# MainBoard_Motor2.net
KiCad netlist of a schematic drawn in Altium Designer
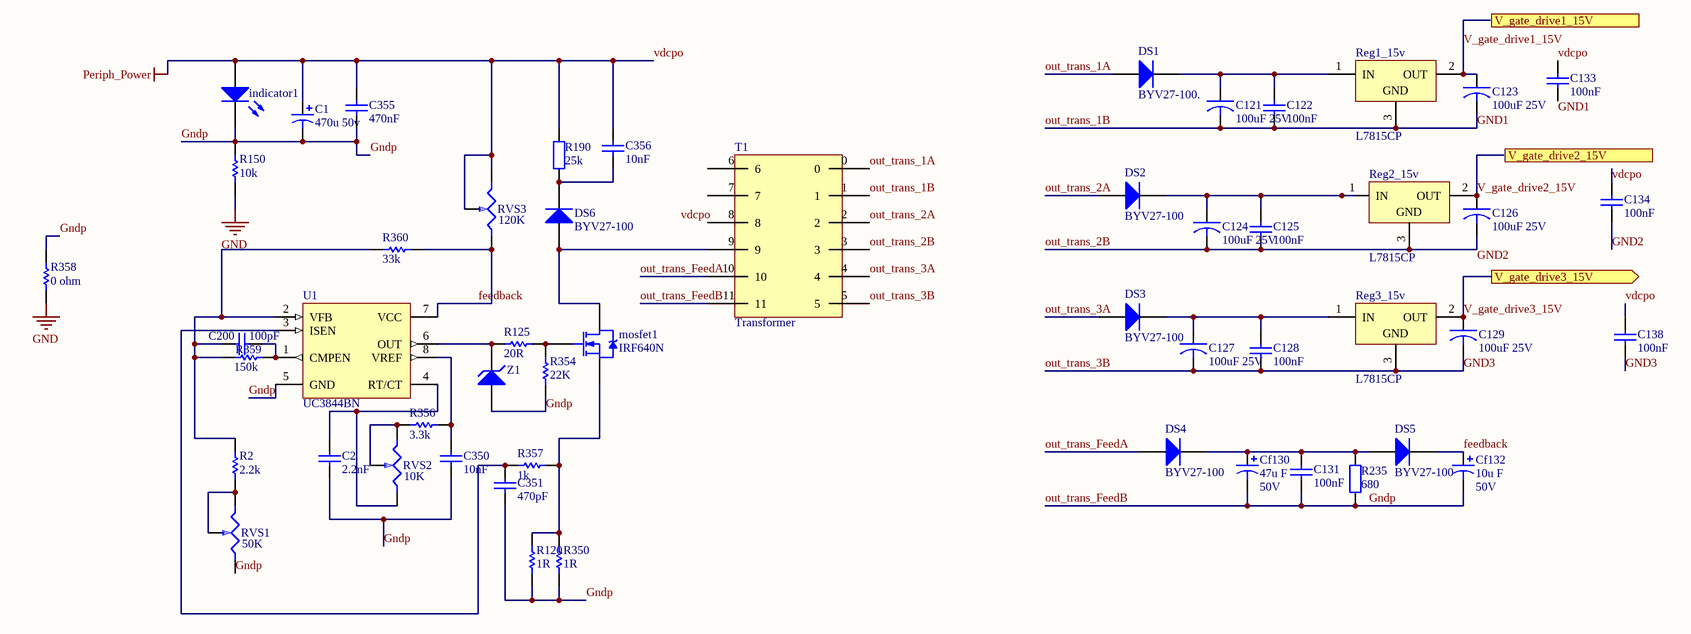
[diagram p0: MainBoard_Motor2.SchDoc]

(export (version "E")
  (design (tool "Eeschema 10.0.6"))
  (components
    (comp (ref "C1")
      (value "470u 50v")
      (footprint "CAPPR5-5x5")
      (description "Polarized Capacitor (Radial)")
      (fields (field (name "PUBLISHER") "Altium Limited"))
      (libsource (lib "Miscellaneous Devices") (part "Cap Pol1"))
    )
    (comp (ref "C2")
      (value "2.2nF")
      (footprint "C0805")
      (description "Cap_2.2nF_10%_X7R_50V_0805")
      (fields (field (name "MANUFACTURER") "Yageo") (field (name "MFR PART NO") "CC0805KRX7R9BB103"))
      (libsource (lib "EVIDC") (part "Cap_10nF_50V_0805"))
    )
    (comp (ref "C121")
      (value "100uF 25V")
      (footprint "EVIDC:CAP_E_6.3x9_2.5")
      (description "Cap_100uF 25V_Pitch2.5mm")
      (fields (field (name "MFR PART NO") "ERS1EM101E11OT") (field (name "MANUFACTURER") "AIHUA"))
      (libsource (lib "EVIDC") (part "Cap_100uF 25V_EL_6.3MM"))
    )
    (comp (ref "C122")
      (value "100nF")
      (footprint "C0805")
      (description "Cap_10nF_10%_X7R_50V_0805")
      (fields (field (name "MANUFACTURER") "Yageo") (field (name "MFR PART NO") "CC0805KRX7R9BB103"))
      (libsource (lib "EVIDC") (part "Cap_10nF_50V_0805"))
    )
    (comp (ref "C123")
      (value "100uF 25V")
      (footprint "EVIDC:CAP_E_6.3x9_2.5")
      (description "Cap_100uF 25V_Pitch2.5mm")
      (fields (field (name "MFR PART NO") "ERS1EM101E11OT") (field (name "MANUFACTURER") "AIHUA"))
      (libsource (lib "EVIDC") (part "Cap_100uF 25V_EL_6.3MM"))
    )
    (comp (ref "C124")
      (value "100uF 25V")
      (footprint "EVIDC:CAP_E_6.3x9_2.5")
      (description "Cap_100uF 25V_Pitch2.5mm")
      (fields (field (name "MFR PART NO") "ERS1EM101E11OT") (field (name "MANUFACTURER") "AIHUA"))
      (libsource (lib "EVIDC") (part "Cap_100uF 25V_EL_6.3MM"))
    )
    (comp (ref "C125")
      (value "100nF")
      (footprint "C0805")
      (description "Cap_10nF_10%_X7R_50V_0805")
      (fields (field (name "MANUFACTURER") "Yageo") (field (name "MFR PART NO") "CC0805KRX7R9BB103"))
      (libsource (lib "EVIDC") (part "Cap_10nF_50V_0805"))
    )
    (comp (ref "C126")
      (value "100uF 25V")
      (footprint "EVIDC:CAP_E_6.3x9_2.5")
      (description "Cap_100uF 25V_Pitch2.5mm")
      (fields (field (name "MFR PART NO") "ERS1EM101E11OT") (field (name "MANUFACTURER") "AIHUA"))
      (libsource (lib "EVIDC") (part "Cap_100uF 25V_EL_6.3MM"))
    )
    (comp (ref "C127")
      (value "100uF 25V")
      (footprint "EVIDC:CAP_E_6.3x9_2.5")
      (description "Cap_100uF 25V_Pitch2.5mm")
      (fields (field (name "MFR PART NO") "ERS1EM101E11OT") (field (name "MANUFACTURER") "AIHUA"))
      (libsource (lib "EVIDC") (part "Cap_100uF 25V_EL_6.3MM"))
    )
    (comp (ref "C128")
      (value "100nF")
      (footprint "C0805")
      (description "Cap_10nF_10%_X7R_50V_0805")
      (fields (field (name "MANUFACTURER") "Yageo") (field (name "MFR PART NO") "CC0805KRX7R9BB103"))
      (libsource (lib "EVIDC") (part "Cap_10nF_50V_0805"))
    )
    (comp (ref "C129")
      (value "100uF 25V")
      (footprint "EVIDC:CAP_E_6.3x9_2.5")
      (description "Cap_100uF 25V_Pitch2.5mm")
      (fields (field (name "MFR PART NO") "ERS1EM101E11OT") (field (name "MANUFACTURER") "AIHUA"))
      (libsource (lib "EVIDC") (part "Cap_100uF 25V_EL_6.3MM"))
    )
    (comp (ref "C131")
      (value "100nF")
      (footprint "C0805")
      (description "Cap_10nF_10%_X7R_50V_0805")
      (fields (field (name "MANUFACTURER") "Yageo") (field (name "MFR PART NO") "CC0805KRX7R9BB103"))
      (libsource (lib "EVIDC") (part "Cap_10nF_50V_0805"))
    )
    (comp (ref "C133")
      (value "100nF")
      (footprint "C0805")
      (description "Cap_10nF_10%_X7R_50V_0805")
      (fields (field (name "MANUFACTURER") "Yageo") (field (name "MFR PART NO") "CC0805KRX7R9BB103"))
      (libsource (lib "EVIDC") (part "Cap_10nF_50V_0805"))
    )
    (comp (ref "C134")
      (value "100nF")
      (footprint "C0805")
      (description "Cap_10nF_10%_X7R_50V_0805")
      (fields (field (name "MANUFACTURER") "Yageo") (field (name "MFR PART NO") "CC0805KRX7R9BB103"))
      (libsource (lib "EVIDC") (part "Cap_10nF_50V_0805"))
    )
    (comp (ref "C138")
      (value "100nF")
      (footprint "C0805")
      (description "Cap_10nF_10%_X7R_50V_0805")
      (fields (field (name "MANUFACTURER") "Yageo") (field (name "MFR PART NO") "CC0805KRX7R9BB103"))
      (libsource (lib "EVIDC") (part "Cap_10nF_50V_0805"))
    )
    (comp (ref "C200")
      (value "100pF")
      (footprint "EVIDC:C0805")
      (description "Cap_100pF_10%_X7R_50V_0805")
      (fields (field (name "MANUFACTURER") "Yageo") (field (name "MFR PART NO") "CC0805KRX7R9BB101"))
      (libsource (lib "EVIDC") (part "Cap_100pF_50V_0805"))
    )
    (comp (ref "C350")
      (value "10nF")
      (footprint "C0805")
      (description "Cap_10nF_10%_X7R_50V_0805")
      (fields (field (name "MANUFACTURER") "Yageo") (field (name "MFR PART NO") "CC0805KRX7R9BB103"))
      (libsource (lib "EVIDC") (part "Cap_10nF_50V_0805"))
    )
    (comp (ref "C351")
      (value "470pF")
      (footprint "C0805")
      (description "Cap_10nF_10%_X7R_50V_0805")
      (fields (field (name "MANUFACTURER") "Yageo") (field (name "MFR PART NO") "CC0805KRX7R9BB103"))
      (libsource (lib "EVIDC") (part "Cap_10nF_50V_0805"))
    )
    (comp (ref "C355")
      (value "470nF")
      (footprint "C0805")
      (description "Cap_10nF_10%_X7R_50V_0805")
      (fields (field (name "MANUFACTURER") "Yageo") (field (name "MFR PART NO") "CC0805KRX7R9BB103"))
      (libsource (lib "EVIDC") (part "Cap_10nF_50V_0805"))
    )
    (comp (ref "C356")
      (value "10nF")
      (footprint "C0805")
      (description "Cap_10nF_10%_X7R_50V_0805")
      (fields (field (name "MANUFACTURER") "Yageo") (field (name "MFR PART NO") "CC0805KRX7R9BB103"))
      (libsource (lib "EVIDC") (part "Cap_10nF_50V_0805"))
    )
    (comp (ref "Cf130")
      (value "47u F")
      (footprint "B")
      (description "Polarized Capacitor (Radial)")
      (fields (field (name "ALTIUM_VALUE") "50V") (field (name "PUBLISHER") "Altium Limited"))
      (libsource (lib "Miscellaneous Devices") (part "Cap Pol1"))
    )
    (comp (ref "Cf132")
      (value "10u F")
      (footprint "B")
      (description "Polarized Capacitor (Radial)")
      (fields (field (name "ALTIUM_VALUE") "50V") (field (name "PUBLISHER") "Altium Limited"))
      (libsource (lib "Miscellaneous Devices") (part "Cap Pol1"))
    )
    (comp (ref "DS1")
      (value "BYV27-100.")
      (footprint "DO-41")
      (description "1 Amp General Purpose Rectifier SMD")
      (fields (field (name "PUBLISHER") "Altium Limited"))
      (libsource (lib "Miscellaneous Devices") (part "Diode 1N4007"))
    )
    (comp (ref "DS2")
      (value "BYV27-100")
      (footprint "DO-41")
      (description "1 Amp General Purpose Rectifier SMD")
      (fields (field (name "PUBLISHER") "Altium Limited"))
      (libsource (lib "Miscellaneous Devices") (part "Diode 1N4007"))
    )
    (comp (ref "DS3")
      (value "BYV27-100")
      (footprint "DO-41")
      (description "1 Amp General Purpose Rectifier SMD")
      (fields (field (name "PUBLISHER") "Altium Limited"))
      (libsource (lib "Miscellaneous Devices") (part "Diode 1N4007"))
    )
    (comp (ref "DS4")
      (value "BYV27-100")
      (footprint "DO-41")
      (description "1 Amp General Purpose Rectifier SMD")
      (fields (field (name "PUBLISHER") "Altium Limited"))
      (libsource (lib "Miscellaneous Devices") (part "Diode 1N4007"))
    )
    (comp (ref "DS5")
      (value "BYV27-100")
      (footprint "DO-41")
      (description "1 Amp General Purpose Rectifier SMD")
      (fields (field (name "PUBLISHER") "Altium Limited"))
      (libsource (lib "Miscellaneous Devices") (part "Diode 1N4007"))
    )
    (comp (ref "DS6")
      (value "BYV27-100")
      (footprint "DO-41")
      (description "1 Amp General Purpose Rectifier")
      (fields (field (name "PUBLISHER") "Altium Limited"))
      (libsource (lib "Miscellaneous Devices") (part "Diode 1N4007"))
    )
    (comp (ref "indicator1")
      (value "GREEN")
      (footprint "EVIDC:LED_0805_GREEN")
      (description "Typical BLUE SiC LED")
      (fields
        (field (name "MANUFACTURER") "Kingbright")
        (field (name "MFR PART NO") "APT2012SGC")
        (field (name "PUBLISHER") "Altium Limited")
      )
      (libsource (lib "Miscellaneous Devices") (part "LED3"))
    )
    (comp (ref "mosfet1")
      (value "IRF640N")
      (footprint "TO-220AB")
      (description "HEXFET Power MOSFET")
      (fields (field (name "PUBLISHER") "Altium Limited"))
      (libsource (lib "IR Discrete MOSFET - Power") (part "IRF640N"))
    )
    (comp (ref "R2")
      (value "2.2k")
      (footprint "EVIDC:R0805")
      (description "Res_2.2K_1%_0805")
      (fields (field (name "MANUFACTURER") "Yageo") (field (name "MFR PART NO") "RC0805FR-074K7L"))
      (libsource (lib "EVIDC") (part "Res_4.7K_0805"))
    )
    (comp (ref "R120")
      (value "1R")
      (footprint "EVIDC:R1206")
      (description "Res_2.2R_1%_1206")
      (fields (field (name "MANUFACTURER") "Yageo") (field (name "MFR PART NO") "RC1206FR-072R2L"))
      (libsource (lib "EVIDC") (part "Res_2.2R_1206"))
    )
    (comp (ref "R125")
      (value "20R")
      (footprint "EVIDC:R1206")
      (description "Res_20R_1%_0.25W_1206")
      (fields (field (name "MANUFACTURER") "Yageo") (field (name "MFR PART NO") "RC1206FR-0720RL"))
      (libsource (lib "EVIDC") (part "Res_20R_1206"))
    )
    (comp (ref "R150")
      (value "10k")
      (footprint "EVIDC:R1206")
      (description "Res_20R_1%_0.25W_1206")
      (fields (field (name "MANUFACTURER") "Yageo") (field (name "MFR PART NO") "RC1206FR-0720RL"))
      (libsource (lib "EVIDC") (part "Res_20R_1206"))
    )
    (comp (ref "R190")
      (value "25k")
      (footprint "AXIAL-0.6")
      (description "Resistor")
      (fields (field (name "PUBLISHER") "Altium Limited"))
      (libsource (lib "Miscellaneous Devices") (part "Res2"))
    )
    (comp (ref "R235")
      (value "680")
      (footprint "AXIAL-0.5")
      (description "Resistor")
      (fields (field (name "PUBLISHER") "Altium Limited"))
      (libsource (lib "Miscellaneous Devices") (part "Res2"))
    )
    (comp (ref "R350")
      (value "1R")
      (footprint "EVIDC:R1206")
      (description "Res_2.2R_1%_1206")
      (fields (field (name "MANUFACTURER") "Yageo") (field (name "MFR PART NO") "RC1206FR-072R2L"))
      (libsource (lib "EVIDC") (part "Res_2.2R_1206"))
    )
    (comp (ref "R354")
      (value "22K")
      (footprint "EVIDC:R0805")
      (description "Res_4.7K_1%_0805")
      (fields (field (name "MANUFACTURER") "Yageo") (field (name "MFR PART NO") "RC0805FR-074K7L"))
      (libsource (lib "EVIDC") (part "Res_4.7K_0805"))
    )
    (comp (ref "R356")
      (value "3.3k")
      (footprint "EVIDC:R0805")
      (description "Res_2.2K_1%_0805")
      (fields (field (name "MANUFACTURER") "Yageo") (field (name "MFR PART NO") "RC0805FR-074K7L"))
      (libsource (lib "EVIDC") (part "Res_4.7K_0805"))
    )
    (comp (ref "R357")
      (value "1k")
      (footprint "EVIDC:R0805")
      (description "Res_2.2K_1%_0805")
      (fields (field (name "MANUFACTURER") "Yageo") (field (name "MFR PART NO") "RC0805FR-074K7L"))
      (libsource (lib "EVIDC") (part "Res_4.7K_0805"))
    )
    (comp (ref "R358")
      (value "0 ohm")
      (footprint "EVIDC:R0805")
      (description "Res_2.2K_1%_0805")
      (fields (field (name "MANUFACTURER") "Yageo") (field (name "MFR PART NO") "RC0805FR-074K7L"))
      (libsource (lib "EVIDC") (part "Res_4.7K_0805"))
    )
    (comp (ref "R359")
      (value "150k")
      (footprint "EVIDC:R1206")
      (description "Res_20R_1%_0.25W_1206")
      (fields (field (name "MANUFACTURER") "Yageo") (field (name "MFR PART NO") "RC1206FR-0720RL"))
      (libsource (lib "EVIDC") (part "Res_20R_1206"))
    )
    (comp (ref "R360")
      (value "33k")
      (footprint "EVIDC:R1206")
      (description "Res_20R_1%_0.25W_1206")
      (fields (field (name "MANUFACTURER") "Yageo") (field (name "MFR PART NO") "RC1206FR-0720RL"))
      (libsource (lib "EVIDC") (part "Res_20R_1206"))
    )
    (comp (ref "Reg1_15v")
      (value "L7815CP")
      (footprint "TO220VW")
      (description "2A Positive Voltage Regulator")
      (fields (field (name "PUBLISHER") "Altium Limited"))
      (libsource (lib "ST Power Mgt Voltage Regulator") (part "L78S05CV"))
    )
    (comp (ref "Reg2_15v")
      (value "L7815CP")
      (footprint "TO220VW")
      (description "2A Positive Voltage Regulator")
      (fields (field (name "PUBLISHER") "Altium Limited"))
      (libsource (lib "ST Power Mgt Voltage Regulator") (part "L78S05CV"))
    )
    (comp (ref "Reg3_15v")
      (value "L7815CP")
      (footprint "TO220VW")
      (description "2A Positive Voltage Regulator")
      (fields (field (name "PUBLISHER") "Altium Limited"))
      (libsource (lib "ST Power Mgt Voltage Regulator") (part "L78S05CV"))
    )
    (comp (ref "RVS1") (value "50K") (footprint "VR5") (libsource (lib "*") (part "RESISTOR VAR")))
    (comp (ref "RVS2") (value "10K") (footprint "VR5") (libsource (lib "*") (part "RESISTOR VAR")))
    (comp (ref "RVS3") (value "120K") (footprint "VR5") (libsource (lib "*") (part "RESISTOR VAR")))
    (comp (ref "T1") (value "Transformer") (libsource (lib "Integrated_Library2") (part "Component_1")))
    (comp (ref "U1")
      (value "UC3844BN")
      (footprint "626-05")
      (description "High Performance Current Mode Controller")
      (fields (field (name "PUBLISHER") "Altium Limited"))
      (libsource (lib "ON Semi Power Mgt DC-DC Converter") (part "UC3844BN"))
    )
    (comp (ref "Z1")
      (value "D Zener")
      (footprint "DO-35")
      (description "Half Watt Zener")
      (fields (field (name "PUBLISHER") "Altium Limited"))
      (libsource (lib "FSC Discrete Diode") (part "1N751A"))
    )
  )
  (nets
    (net (code "1") (name "/GND1") (class "Default")
      (node (ref "C121") (pin "2") (pinfunction "2_2") (pintype "passive"))
      (node (ref "C122") (pin "1") (pinfunction "1_1") (pintype "passive"))
      (node (ref "C123") (pin "2") (pinfunction "2_2") (pintype "passive"))
      (node (ref "Reg1_15v") (pin "3") (pinfunction "GND_3") (pintype "power_in"))
      (node (ref "T1") (pin "1") (pinfunction "1_1") (pintype "passive"))
    )
    (net (code "2") (name "/GND2") (class "Default")
      (node (ref "C134") (pin "1") (pinfunction "1_1") (pintype "passive"))
    )
    (net (code "3") (name "/GND3") (class "Default")
      (node (ref "C127") (pin "2") (pinfunction "2_2") (pintype "passive"))
      (node (ref "C128") (pin "1") (pinfunction "1_1") (pintype "passive"))
      (node (ref "C129") (pin "2") (pinfunction "2_2") (pintype "passive"))
      (node (ref "C138") (pin "1") (pinfunction "1_1") (pintype "passive"))
      (node (ref "Reg3_15v") (pin "3") (pinfunction "GND_3") (pintype "power_in"))
      (node (ref "T1") (pin "5") (pinfunction "5_5") (pintype "passive"))
    )
    (net (code "4") (name "/Gndp") (class "Default")
      (node (ref "C1") (pin "2") (pinfunction "2_2") (pintype "passive"))
      (node (ref "C131") (pin "1") (pinfunction "1_1") (pintype "passive"))
      (node (ref "C2") (pin "1") (pinfunction "1_1") (pintype "passive"))
      (node (ref "C350") (pin "1") (pinfunction "1_1") (pintype "passive"))
      (node (ref "C351") (pin "1") (pinfunction "1_1") (pintype "passive"))
      (node (ref "C355") (pin "1") (pinfunction "1_1") (pintype "passive"))
      (node (ref "Cf130") (pin "2") (pinfunction "2_2") (pintype "passive"))
      (node (ref "Cf132") (pin "2") (pinfunction "2_2") (pintype "passive"))
      (node (ref "R120") (pin "2") (pinfunction "2_2") (pintype "passive"))
      (node (ref "R150") (pin "2") (pinfunction "2_2") (pintype "passive"))
      (node (ref "R235") (pin "1") (pinfunction "1_1") (pintype "passive"))
      (node (ref "R350") (pin "2") (pinfunction "2_2") (pintype "passive"))
      (node (ref "R354") (pin "1") (pinfunction "1_1") (pintype "passive"))
      (node (ref "R358") (pin "2") (pinfunction "2_2") (pintype "passive"))
      (node (ref "RVS1") (pin "3") (pinfunction "B_3") (pintype "passive"))
      (node (ref "T1") (pin "11") (pinfunction "11_11") (pintype "passive"))
      (node (ref "U1") (pin "5") (pinfunction "GND_5") (pintype "power_in"))
      (node (ref "Z1") (pin "1") (pinfunction "A_1") (pintype "passive"))
      (node (ref "indicator1") (pin "2") (pinfunction "K_2") (pintype "passive"))
    )
    (net (code "5") (name "/V_gate_drive1_15V") (class "Default")
      (node (ref "C123") (pin "1") (pinfunction "1_1") (pintype "passive"))
      (node (ref "Reg1_15v") (pin "2") (pinfunction "OUT_2") (pintype "power_in"))
    )
    (net (code "6") (name "/V_gate_drive2_15V") (class "Default")
      (node (ref "C126") (pin "1") (pinfunction "1_1") (pintype "passive"))
      (node (ref "Reg2_15v") (pin "2") (pinfunction "OUT_2") (pintype "power_in"))
    )
    (net (code "7") (name "/V_gate_drive3_15V") (class "Default")
      (node (ref "C129") (pin "1") (pinfunction "1_1") (pintype "passive"))
      (node (ref "Reg3_15v") (pin "2") (pinfunction "OUT_2") (pintype "power_in"))
    )
    (net (code "8") (name "/feedback") (class "Default")
      (node (ref "Cf132") (pin "1") (pinfunction "1_1") (pintype "passive"))
      (node (ref "DS5") (pin "2") (pinfunction "K_2") (pintype "passive"))
      (node (ref "R360") (pin "2") (pinfunction "2_2") (pintype "passive"))
      (node (ref "RVS3") (pin "3") (pinfunction "B_3") (pintype "passive"))
      (node (ref "U1") (pin "7") (pinfunction "VCC_7") (pintype "power_in"))
    )
    (net (code "9") (name "/out_trans_1A") (class "Default")
      (node (ref "DS1") (pin "1") (pinfunction "A_1") (pintype "passive"))
      (node (ref "T1") (pin "0") (pinfunction "0_0") (pintype "passive"))
    )
    (net (code "10") (name "/out_trans_2A") (class "Default")
      (node (ref "DS2") (pin "1") (pinfunction "A_1") (pintype "passive"))
      (node (ref "T1") (pin "2") (pinfunction "2_2") (pintype "passive"))
    )
    (net (code "11") (name "/out_trans_2B") (class "Default")
      (node (ref "C124") (pin "2") (pinfunction "2_2") (pintype "passive"))
      (node (ref "C125") (pin "1") (pinfunction "1_1") (pintype "passive"))
      (node (ref "C126") (pin "2") (pinfunction "2_2") (pintype "passive"))
      (node (ref "Reg2_15v") (pin "3") (pinfunction "GND_3") (pintype "power_in"))
      (node (ref "T1") (pin "3") (pinfunction "3_3") (pintype "passive"))
    )
    (net (code "12") (name "/out_trans_3A") (class "Default")
      (node (ref "DS3") (pin "1") (pinfunction "A_1") (pintype "passive"))
      (node (ref "T1") (pin "4") (pinfunction "4_4") (pintype "passive"))
    )
    (net (code "13") (name "/out_trans_FeedA") (class "Default")
      (node (ref "DS4") (pin "1") (pinfunction "A_1") (pintype "passive"))
      (node (ref "T1") (pin "10") (pinfunction "10_10") (pintype "passive"))
    )
    (net (code "14") (name "GND") (class "Default")
      (node (ref "R150") (pin "1") (pinfunction "1_1") (pintype "passive"))
      (node (ref "R358") (pin "1") (pinfunction "1_1") (pintype "passive"))
    )
    (net (code "15") (name "Net-(DS1-K)") (class "Default")
      (node (ref "C121") (pin "1") (pinfunction "1_1") (pintype "passive"))
      (node (ref "C122") (pin "2") (pinfunction "2_2") (pintype "passive"))
      (node (ref "DS1") (pin "2") (pinfunction "K_2") (pintype "passive"))
      (node (ref "Reg1_15v") (pin "1") (pinfunction "IN_1") (pintype "power_in"))
    )
    (net (code "16") (name "Net-(DS2-K)") (class "Default")
      (node (ref "C124") (pin "1") (pinfunction "1_1") (pintype "passive"))
      (node (ref "C125") (pin "2") (pinfunction "2_2") (pintype "passive"))
      (node (ref "DS2") (pin "2") (pinfunction "K_2") (pintype "passive"))
      (node (ref "Reg2_15v") (pin "1") (pinfunction "IN_1") (pintype "power_in"))
    )
    (net (code "17") (name "Net-(DS3-K)") (class "Default")
      (node (ref "C127") (pin "1") (pinfunction "1_1") (pintype "passive"))
      (node (ref "C128") (pin "2") (pinfunction "2_2") (pintype "passive"))
      (node (ref "DS3") (pin "2") (pinfunction "K_2") (pintype "passive"))
      (node (ref "Reg3_15v") (pin "1") (pinfunction "IN_1") (pintype "power_in"))
    )
    (net (code "18") (name "Net-(DS4-K)") (class "Default")
      (node (ref "C131") (pin "2") (pinfunction "2_2") (pintype "passive"))
      (node (ref "Cf130") (pin "1") (pinfunction "1_1") (pintype "passive"))
      (node (ref "DS4") (pin "2") (pinfunction "K_2") (pintype "passive"))
      (node (ref "DS5") (pin "1") (pinfunction "A_1") (pintype "passive"))
      (node (ref "R235") (pin "2") (pinfunction "2_2") (pintype "passive"))
    )
    (net (code "19") (name "Net-(DS6-A)") (class "Default")
      (node (ref "DS6") (pin "1") (pinfunction "A_1") (pintype "passive"))
      (node (ref "T1") (pin "9") (pinfunction "9_9") (pintype "passive"))
      (node (ref "mosfet1") (pin "2") (pinfunction "D_2") (pintype "passive"))
    )
    (net (code "20") (name "Net-(DS6-K)") (class "Default")
      (node (ref "C356") (pin "1") (pinfunction "1_1") (pintype "passive"))
      (node (ref "DS6") (pin "2") (pinfunction "K_2") (pintype "passive"))
      (node (ref "R190") (pin "1") (pinfunction "1_1") (pintype "passive"))
    )
    (net (code "21") (name "Net-(RVS1-A)") (class "Default")
      (node (ref "R2") (pin "1") (pinfunction "1_1") (pintype "passive"))
      (node (ref "RVS1") (pin "1") (pinfunction "A_1") (pintype "passive"))
      (node (ref "RVS1") (pin "2") (pinfunction "WIPER_2") (pintype "passive"))
    )
    (net (code "22") (name "Net-(RVS2-A)") (class "Default")
      (node (ref "R356") (pin "1") (pinfunction "1_1") (pintype "passive"))
      (node (ref "RVS2") (pin "1") (pinfunction "A_1") (pintype "passive"))
      (node (ref "RVS2") (pin "2") (pinfunction "WIPER_2") (pintype "passive"))
    )
    (net (code "23") (name "Net-(RVS2-B)") (class "Default")
      (node (ref "C2") (pin "2") (pinfunction "2_2") (pintype "passive"))
      (node (ref "RVS2") (pin "3") (pinfunction "B_3") (pintype "passive"))
      (node (ref "U1") (pin "4") (pinfunction "RT/CT_4") (pintype "passive"))
    )
    (net (code "24") (name "Net-(U1-CMPEN)") (class "Default")
      (node (ref "C200") (pin "2") (pinfunction "2_2") (pintype "passive"))
      (node (ref "R359") (pin "2") (pinfunction "2_2") (pintype "passive"))
      (node (ref "U1") (pin "1") (pinfunction "CMPEN_1") (pintype "output"))
    )
    (net (code "25") (name "Net-(U1-ISEN)") (class "Default")
      (node (ref "C351") (pin "2") (pinfunction "2_2") (pintype "passive"))
      (node (ref "R357") (pin "1") (pinfunction "1_1") (pintype "passive"))
      (node (ref "U1") (pin "3") (pinfunction "ISEN_3") (pintype "input"))
    )
    (net (code "26") (name "Net-(U1-OUT)") (class "Default")
      (node (ref "R125") (pin "1") (pinfunction "1_1") (pintype "passive"))
      (node (ref "U1") (pin "6") (pinfunction "OUT_6") (pintype "output"))
      (node (ref "Z1") (pin "2") (pinfunction "K_2") (pintype "passive"))
    )
    (net (code "27") (name "Net-(U1-VFB)") (class "Default")
      (node (ref "C200") (pin "1") (pinfunction "1_1") (pintype "passive"))
      (node (ref "R2") (pin "2") (pinfunction "2_2") (pintype "passive"))
      (node (ref "R359") (pin "1") (pinfunction "1_1") (pintype "passive"))
      (node (ref "R360") (pin "1") (pinfunction "1_1") (pintype "passive"))
      (node (ref "U1") (pin "2") (pinfunction "VFB_2") (pintype "input"))
    )
    (net (code "28") (name "Net-(U1-VREF)") (class "Default")
      (node (ref "C350") (pin "2") (pinfunction "2_2") (pintype "passive"))
      (node (ref "R356") (pin "2") (pinfunction "2_2") (pintype "passive"))
      (node (ref "U1") (pin "8") (pinfunction "VREF_8") (pintype "output"))
    )
    (net (code "29") (name "Net-(mosfet1-G)") (class "Default")
      (node (ref "R125") (pin "2") (pinfunction "2_2") (pintype "passive"))
      (node (ref "R354") (pin "2") (pinfunction "2_2") (pintype "passive"))
      (node (ref "mosfet1") (pin "1") (pinfunction "G_1") (pintype "passive"))
    )
    (net (code "30") (name "Net-(mosfet1-S)") (class "Default")
      (node (ref "R120") (pin "1") (pinfunction "1_1") (pintype "passive"))
      (node (ref "R350") (pin "1") (pinfunction "1_1") (pintype "passive"))
      (node (ref "R357") (pin "2") (pinfunction "2_2") (pintype "passive"))
      (node (ref "mosfet1") (pin "3") (pinfunction "S_3") (pintype "passive"))
    )
    (net (code "31") (name "Periph_Power") (class "Default")
      (node (ref "C1") (pin "1") (pinfunction "1_1") (pintype "passive"))
      (node (ref "C133") (pin "2") (pinfunction "2_2") (pintype "passive"))
      (node (ref "C134") (pin "2") (pinfunction "2_2") (pintype "passive"))
      (node (ref "C138") (pin "2") (pinfunction "2_2") (pintype "passive"))
      (node (ref "C355") (pin "2") (pinfunction "2_2") (pintype "passive"))
      (node (ref "C356") (pin "2") (pinfunction "2_2") (pintype "passive"))
      (node (ref "R190") (pin "2") (pinfunction "2_2") (pintype "passive"))
      (node (ref "RVS3") (pin "1") (pinfunction "A_1") (pintype "passive"))
      (node (ref "RVS3") (pin "2") (pinfunction "WIPER_2") (pintype "passive"))
      (node (ref "indicator1") (pin "1") (pinfunction "A_1") (pintype "passive"))
    )
    (net (code "32") (name "unconnected-(C133-Pad1)") (class "Default")
      (node (ref "C133") (pin "1") (pinfunction "1_1") (pintype "passive"))
    )
    (net (code "33") (name "unconnected-(T1-Pad6)") (class "Default")
      (node (ref "T1") (pin "6") (pinfunction "6_6") (pintype "passive"))
    )
    (net (code "34") (name "unconnected-(T1-Pad7)") (class "Default")
      (node (ref "T1") (pin "7") (pinfunction "7_7") (pintype "passive"))
    )
    (net (code "35") (name "unconnected-(T1-Pad8)") (class "Default")
      (node (ref "T1") (pin "8") (pinfunction "8_8") (pintype "passive"))
    )
  )
)
